# Audio-Beamformer_RaspberryPi_V1_0.net
KiCad netlist of a schematic drawn in Altium Designer
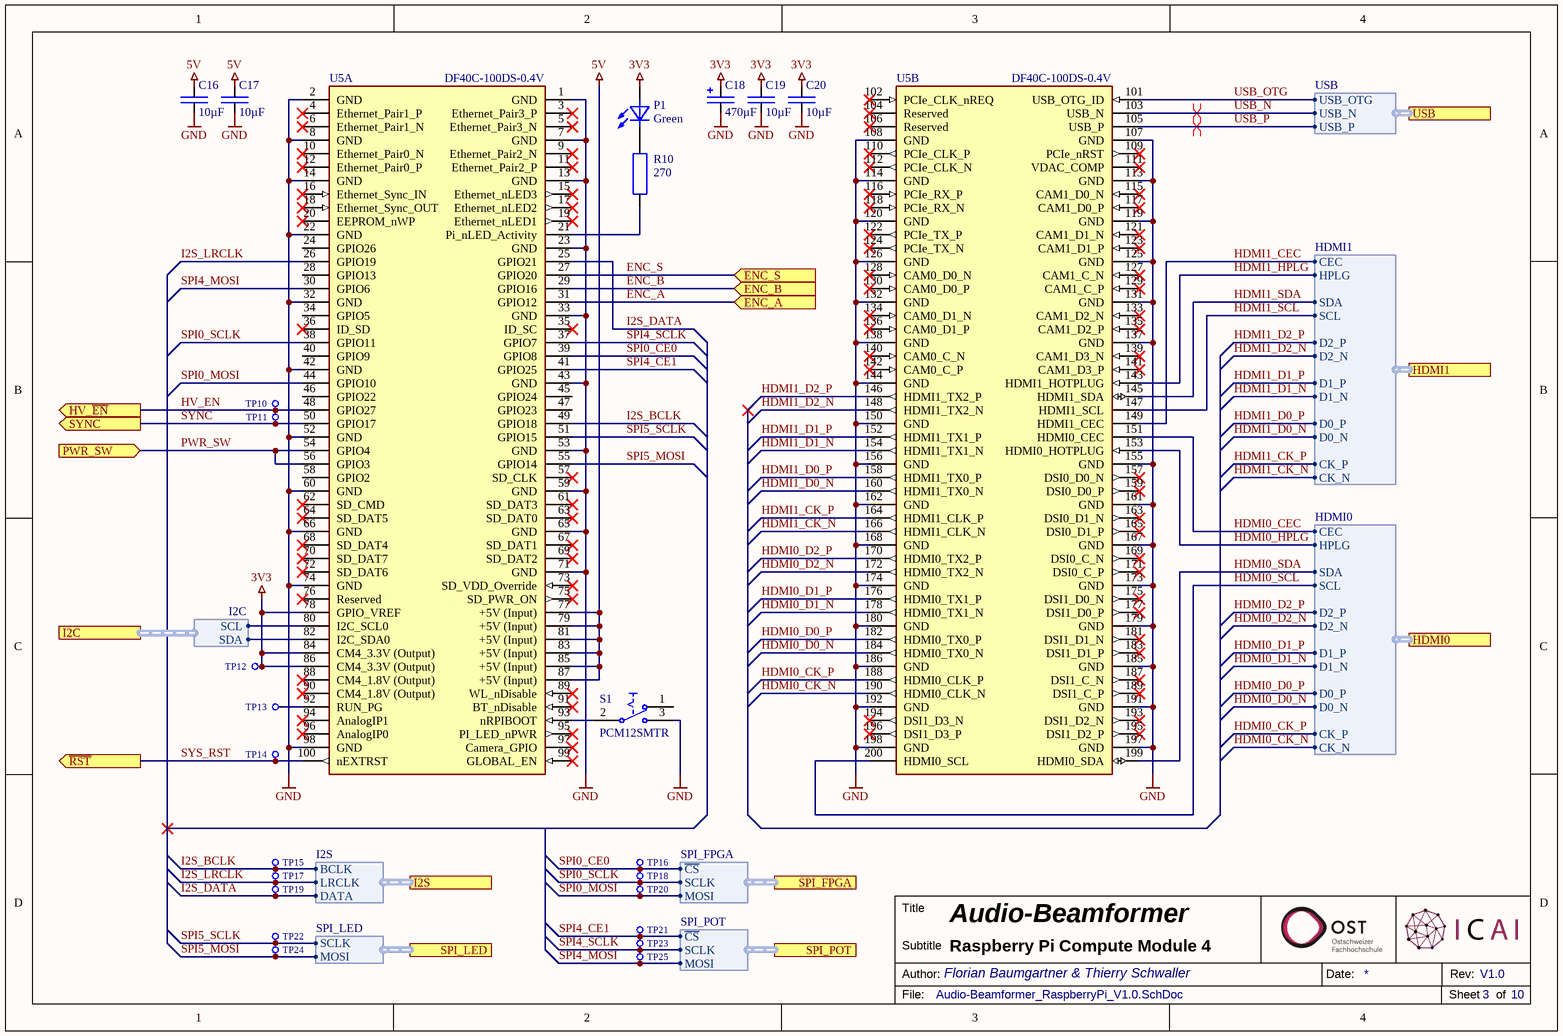
[diagram p0: Audio-Beamformer_RaspberryPi_V1.0.SchDoc]

(export (version "E")
  (design (tool "Eeschema 10.0.6"))
  (components
    (comp (ref "C16")
      (value "10µF")
      (footprint "SMD Keramikkondensator 1206")
      (description "CAP-MK")
      (libsource (lib "AudioAmp") (part "C-CAPACITOR"))
    )
    (comp (ref "C17")
      (value "10µF")
      (footprint "SMD Keramikkondensator 1206")
      (description "CAP-MK")
      (libsource (lib "AudioAmp") (part "C-CAPACITOR"))
    )
    (comp (ref "C18")
      (value "470µF")
      (footprint "SMD Elko 10.0x10.0")
      (description "CAP-Elko")
      (libsource (lib "TFS Integrated Library") (part "C-ELCAP"))
    )
    (comp (ref "C19")
      (value "10µF")
      (footprint "SMD Keramikkondensator 1206")
      (description "CAP-MK")
      (libsource (lib "AudioAmp") (part "C-CAPACITOR"))
    )
    (comp (ref "C20")
      (value "10µF")
      (footprint "SMD Keramikkondensator 1206")
      (description "CAP-MK")
      (libsource (lib "AudioAmp") (part "C-CAPACITOR"))
    )
    (comp (ref "P1")
      (value "Green")
      (footprint "SMD LED 0603")
      (description "General Purpose LED")
      (libsource (lib "Fleet-Monitor") (part "LED Green 0603"))
    )
    (comp (ref "R10")
      (value "270")
      (footprint "SMD Widerstand 0603")
      (description "SMD-Widerstand 1/4W")
      (libsource (lib "Backplane_1") (part "R-RESISTOR"))
    )
    (comp (ref "S1")
      (value "PCM12SMTR")
      (footprint "SMD Switch SPDT (PCM12SMTR)")
      (description "Miniature Slide Switch")
      (libsource (lib "Custom ST-Link") (part "S-PCM12SMTR"))
    )
    (comp (ref "TP10")
      (value "X-TP")
      (footprint "THT Testpunkt Ø1mm")
      (description "Testpunkt")
      (libsource (lib "Teensy-DevBoard") (part "X-TP"))
    )
    (comp (ref "TP11")
      (value "X-TP")
      (footprint "THT Testpunkt Ø1mm")
      (description "Testpunkt")
      (libsource (lib "Teensy-DevBoard") (part "X-TP"))
    )
    (comp (ref "TP12")
      (value "X-TP")
      (footprint "THT Testpunkt Ø1mm")
      (description "Testpunkt")
      (libsource (lib "Teensy-DevBoard") (part "X-TP"))
    )
    (comp (ref "TP13")
      (value "X-TP")
      (footprint "THT Testpunkt Ø1mm")
      (description "Testpunkt")
      (libsource (lib "Teensy-DevBoard") (part "X-TP"))
    )
    (comp (ref "TP14")
      (value "X-TP")
      (footprint "THT Testpunkt Ø1mm")
      (description "Testpunkt")
      (libsource (lib "Teensy-DevBoard") (part "X-TP"))
    )
    (comp (ref "TP15")
      (value "X-TP")
      (footprint "THT Testpunkt Ø1mm")
      (description "Testpunkt")
      (libsource (lib "Teensy-DevBoard") (part "X-TP"))
    )
    (comp (ref "TP16")
      (value "X-TP")
      (footprint "THT Testpunkt Ø1mm")
      (description "Testpunkt")
      (libsource (lib "Teensy-DevBoard") (part "X-TP"))
    )
    (comp (ref "TP17")
      (value "X-TP")
      (footprint "THT Testpunkt Ø1mm")
      (description "Testpunkt")
      (libsource (lib "Teensy-DevBoard") (part "X-TP"))
    )
    (comp (ref "TP18")
      (value "X-TP")
      (footprint "THT Testpunkt Ø1mm")
      (description "Testpunkt")
      (libsource (lib "Teensy-DevBoard") (part "X-TP"))
    )
    (comp (ref "TP19")
      (value "X-TP")
      (footprint "THT Testpunkt Ø1mm")
      (description "Testpunkt")
      (libsource (lib "Teensy-DevBoard") (part "X-TP"))
    )
    (comp (ref "TP20")
      (value "X-TP")
      (footprint "THT Testpunkt Ø1mm")
      (description "Testpunkt")
      (libsource (lib "Teensy-DevBoard") (part "X-TP"))
    )
    (comp (ref "TP21")
      (value "X-TP")
      (footprint "THT Testpunkt Ø1mm")
      (description "Testpunkt")
      (libsource (lib "Teensy-DevBoard") (part "X-TP"))
    )
    (comp (ref "TP22")
      (value "X-TP")
      (footprint "THT Testpunkt Ø1mm")
      (description "Testpunkt")
      (libsource (lib "Teensy-DevBoard") (part "X-TP"))
    )
    (comp (ref "TP23")
      (value "X-TP")
      (footprint "THT Testpunkt Ø1mm")
      (description "Testpunkt")
      (libsource (lib "Teensy-DevBoard") (part "X-TP"))
    )
    (comp (ref "TP24")
      (value "X-TP")
      (footprint "THT Testpunkt Ø1mm")
      (description "Testpunkt")
      (libsource (lib "Teensy-DevBoard") (part "X-TP"))
    )
    (comp (ref "TP25")
      (value "X-TP")
      (footprint "THT Testpunkt Ø1mm")
      (description "Testpunkt")
      (libsource (lib "Teensy-DevBoard") (part "X-TP"))
    )
    (comp (ref "U5")
      (value "DF40C-100DS-0.4V")
      (footprint "SMD CM4-F40C-100DS-0.4v_1.5mm")
      (description "Board-To-Board Connector")
      (libsource (lib "Audio-Beamformer") (part "U-CM4"))
    )
  )
  (nets
    (net (code "9") (name "/ENC_A") (class "Default")
      (node (ref "U5") (pin "31") (pinfunction "GPIO12_31") (pintype "passive"))
    )
    (net (code "10") (name "/ENC_B") (class "Default")
      (node (ref "U5") (pin "29") (pinfunction "GPIO16_29") (pintype "passive"))
    )
    (net (code "11") (name "/ENC_S") (class "Default")
      (node (ref "U5") (pin "27") (pinfunction "GPIO20_27") (pintype "passive"))
    )
    (net (code "12") (name "/HDMI0_CEC") (class "Default")
      (node (ref "U5") (pin "151") (pinfunction "HDMI0_CEC_151") (pintype "open_collector"))
    )
    (net (code "13") (name "/HDMI0_CK_N") (class "Default")
      (node (ref "U5") (pin "190") (pinfunction "HDMI0_CLK_N_190") (pintype "output"))
    )
    (net (code "14") (name "/HDMI0_CK_P") (class "Default")
      (node (ref "U5") (pin "188") (pinfunction "HDMI0_CLK_P_188") (pintype "output"))
    )
    (net (code "15") (name "/HDMI0_D0_N") (class "Default")
      (node (ref "U5") (pin "184") (pinfunction "HDMI0_TX0_N_184") (pintype "output"))
    )
    (net (code "16") (name "/HDMI0_D0_P") (class "Default")
      (node (ref "U5") (pin "182") (pinfunction "HDMI0_TX0_P_182") (pintype "output"))
    )
    (net (code "17") (name "/HDMI0_D1_N") (class "Default")
      (node (ref "U5") (pin "178") (pinfunction "HDMI0_TX1_N_178") (pintype "output"))
    )
    (net (code "18") (name "/HDMI0_D1_P") (class "Default")
      (node (ref "U5") (pin "176") (pinfunction "HDMI0_TX1_P_176") (pintype "output"))
    )
    (net (code "19") (name "/HDMI0_D2_N") (class "Default")
      (node (ref "U5") (pin "172") (pinfunction "HDMI0_TX2_N_172") (pintype "output"))
    )
    (net (code "20") (name "/HDMI0_D2_P") (class "Default")
      (node (ref "U5") (pin "170") (pinfunction "HDMI0_TX2_P_170") (pintype "output"))
    )
    (net (code "21") (name "/HDMI0_HPLG") (class "Default")
      (node (ref "U5") (pin "153") (pinfunction "HDMI0_HOTPLUG_153") (pintype "input"))
    )
    (net (code "22") (name "/HDMI0_SCL") (class "Default")
      (node (ref "U5") (pin "200") (pinfunction "HDMI0_SCL_200") (pintype "open_collector"))
    )
    (net (code "23") (name "/HDMI0_SDA") (class "Default")
      (node (ref "U5") (pin "199") (pinfunction "HDMI0_SDA_199") (pintype "bidirectional"))
    )
    (net (code "24") (name "/HDMI1_CEC") (class "Default")
      (node (ref "U5") (pin "149") (pinfunction "HDMI1_CEC_149") (pintype "open_collector"))
    )
    (net (code "25") (name "/HDMI1_CK_N") (class "Default")
      (node (ref "U5") (pin "166") (pinfunction "HDMI1_CLK_N_166") (pintype "output"))
    )
    (net (code "26") (name "/HDMI1_CK_P") (class "Default")
      (node (ref "U5") (pin "164") (pinfunction "HDMI1_CLK_P_164") (pintype "output"))
    )
    (net (code "27") (name "/HDMI1_D0_N") (class "Default")
      (node (ref "U5") (pin "160") (pinfunction "HDMI1_TX0_N_160") (pintype "output"))
    )
    (net (code "28") (name "/HDMI1_D0_P") (class "Default")
      (node (ref "U5") (pin "158") (pinfunction "HDMI1_TX0_P_158") (pintype "output"))
    )
    (net (code "29") (name "/HDMI1_D1_N") (class "Default")
      (node (ref "U5") (pin "154") (pinfunction "HDMI1_TX1_N_154") (pintype "output"))
    )
    (net (code "30") (name "/HDMI1_D1_P") (class "Default")
      (node (ref "U5") (pin "152") (pinfunction "HDMI1_TX1_P_152") (pintype "output"))
    )
    (net (code "31") (name "/HDMI1_D2_N") (class "Default")
      (node (ref "U5") (pin "148") (pinfunction "HDMI1_TX2_N_148") (pintype "output"))
    )
    (net (code "32") (name "/HDMI1_D2_P") (class "Default")
      (node (ref "U5") (pin "146") (pinfunction "HDMI1_TX2_P_146") (pintype "output"))
    )
    (net (code "33") (name "/HDMI1_HPLG") (class "Default")
      (node (ref "U5") (pin "143") (pinfunction "HDMI1_HOTPLUG_143") (pintype "input"))
    )
    (net (code "34") (name "/HDMI1_SCL") (class "Default")
      (node (ref "U5") (pin "147") (pinfunction "HDMI1_SCL_147") (pintype "open_collector"))
    )
    (net (code "35") (name "/HDMI1_SDA") (class "Default")
      (node (ref "U5") (pin "145") (pinfunction "HDMI1_SDA_145") (pintype "bidirectional"))
    )
    (net (code "36") (name "/HV_EN") (class "Default")
      (node (ref "TP10") (pin "1") (pinfunction "1_1") (pintype "passive"))
      (node (ref "U5") (pin "48") (pinfunction "GPIO27_48") (pintype "passive"))
    )
    (net (code "37") (name "/I2S_BCLK") (class "Default")
      (node (ref "TP15") (pin "1") (pinfunction "1_1") (pintype "passive"))
      (node (ref "U5") (pin "49") (pinfunction "GPIO18_49") (pintype "passive"))
    )
    (net (code "38") (name "/I2S_DATA") (class "Default")
      (node (ref "TP19") (pin "1") (pinfunction "1_1") (pintype "passive"))
      (node (ref "U5") (pin "25") (pinfunction "GPIO21_25") (pintype "passive"))
    )
    (net (code "39") (name "/I2S_LRCLK") (class "Default")
      (node (ref "TP17") (pin "1") (pinfunction "1_1") (pintype "passive"))
      (node (ref "U5") (pin "26") (pinfunction "GPIO19_26") (pintype "passive"))
    )
    (net (code "40") (name "/PWR_SW") (class "Default")
      (node (ref "U5") (pin "54") (pinfunction "GPIO4_54") (pintype "passive"))
      (node (ref "U5") (pin "56") (pinfunction "GPIO3_56") (pintype "passive"))
    )
    (net (code "41") (name "/SPI0_CE0") (class "Default")
      (node (ref "TP16") (pin "1") (pinfunction "1_1") (pintype "passive"))
      (node (ref "U5") (pin "39") (pinfunction "GPIO8_39") (pintype "passive"))
    )
    (net (code "42") (name "/SPI0_MOSI") (class "Default")
      (node (ref "TP20") (pin "1") (pinfunction "1_1") (pintype "passive"))
      (node (ref "U5") (pin "44") (pinfunction "GPIO10_44") (pintype "passive"))
    )
    (net (code "43") (name "/SPI0_SCLK") (class "Default")
      (node (ref "TP18") (pin "1") (pinfunction "1_1") (pintype "passive"))
      (node (ref "U5") (pin "38") (pinfunction "GPIO11_38") (pintype "passive"))
    )
    (net (code "44") (name "/SPI4_CE1") (class "Default")
      (node (ref "TP21") (pin "1") (pinfunction "1_1") (pintype "passive"))
      (node (ref "U5") (pin "41") (pinfunction "GPIO25_41") (pintype "passive"))
    )
    (net (code "45") (name "/SPI4_MOSI") (class "Default")
      (node (ref "TP25") (pin "1") (pinfunction "1_1") (pintype "passive"))
      (node (ref "U5") (pin "30") (pinfunction "GPIO6_30") (pintype "passive"))
    )
    (net (code "46") (name "/SPI4_SCLK") (class "Default")
      (node (ref "TP23") (pin "1") (pinfunction "1_1") (pintype "passive"))
      (node (ref "U5") (pin "37") (pinfunction "GPIO7_37") (pintype "passive"))
    )
    (net (code "47") (name "/SPI5_MOSI") (class "Default")
      (node (ref "TP24") (pin "1") (pinfunction "1_1") (pintype "passive"))
      (node (ref "U5") (pin "55") (pinfunction "GPIO14_55") (pintype "passive"))
    )
    (net (code "48") (name "/SPI5_SCLK") (class "Default")
      (node (ref "TP22") (pin "1") (pinfunction "1_1") (pintype "passive"))
      (node (ref "U5") (pin "51") (pinfunction "GPIO15_51") (pintype "passive"))
    )
    (net (code "49") (name "/SYNC") (class "Default")
      (node (ref "TP11") (pin "1") (pinfunction "1_1") (pintype "passive"))
      (node (ref "U5") (pin "50") (pinfunction "GPIO17_50") (pintype "passive"))
    )
    (net (code "50") (name "/SYS_RST") (class "Default")
      (node (ref "TP14") (pin "1") (pinfunction "1_1") (pintype "passive"))
      (node (ref "U5") (pin "100") (pinfunction "nEXTRST_100") (pintype "output"))
    )
    (net (code "51") (name "/USB_N") (class "Default")
      (node (ref "U5") (pin "103") (pinfunction "USB_N_103") (pintype "passive"))
    )
    (net (code "52") (name "/USB_OTG") (class "Default")
      (node (ref "U5") (pin "101") (pinfunction "USB_OTG_ID_101") (pintype "input"))
    )
    (net (code "53") (name "/USB_P") (class "Default")
      (node (ref "U5") (pin "105") (pinfunction "USB_P_105") (pintype "passive"))
    )
    (net (code "62") (name "3V3") (class "Default")
      (node (ref "C18") (pin "P") (pinfunction "+_P") (pintype "passive"))
      (node (ref "C19") (pin "2") (pinfunction "2_2") (pintype "passive"))
      (node (ref "C20") (pin "2") (pinfunction "2_2") (pintype "passive"))
      (node (ref "P1") (pin "A") (pinfunction "A_A") (pintype "passive"))
      (node (ref "TP12") (pin "1") (pinfunction "1_1") (pintype "passive"))
      (node (ref "U5") (pin "78") (pinfunction "GPIO_VREF_78") (pintype "power_in"))
      (node (ref "U5") (pin "84") (pinfunction "CM4_3.3V_(Output)_84") (pintype "power_in"))
      (node (ref "U5") (pin "86") (pinfunction "CM4_3.3V_(Output)_86") (pintype "power_in"))
    )
    (net (code "63") (name "5V") (class "Default")
      (node (ref "C16") (pin "2") (pinfunction "2_2") (pintype "passive"))
      (node (ref "C17") (pin "2") (pinfunction "2_2") (pintype "passive"))
      (node (ref "U5") (pin "77") (pinfunction "+5V_(Input)_77") (pintype "power_in"))
      (node (ref "U5") (pin "79") (pinfunction "+5V_(Input)_79") (pintype "power_in"))
      (node (ref "U5") (pin "81") (pinfunction "+5V_(Input)_81") (pintype "power_in"))
      (node (ref "U5") (pin "83") (pinfunction "+5V_(Input)_83") (pintype "power_in"))
      (node (ref "U5") (pin "85") (pinfunction "+5V_(Input)_85") (pintype "power_in"))
      (node (ref "U5") (pin "87") (pinfunction "+5V_(Input)_87") (pintype "power_in"))
    )
    (net (code "64") (name "GND") (class "Default")
      (node (ref "C16") (pin "1") (pinfunction "1_1") (pintype "passive"))
      (node (ref "C17") (pin "1") (pinfunction "1_1") (pintype "passive"))
      (node (ref "C18") (pin "M") (pinfunction "-_M") (pintype "passive"))
      (node (ref "C19") (pin "1") (pinfunction "1_1") (pintype "passive"))
      (node (ref "C20") (pin "1") (pinfunction "1_1") (pintype "passive"))
      (node (ref "S1") (pin "3") (pinfunction "NO1_3") (pintype "passive"))
      (node (ref "U5") (pin "1") (pinfunction "GND_1") (pintype "power_in"))
      (node (ref "U5") (pin "107") (pinfunction "GND_107") (pintype "power_in"))
      (node (ref "U5") (pin "108") (pinfunction "GND_108") (pintype "power_in"))
      (node (ref "U5") (pin "113") (pinfunction "GND_113") (pintype "power_in"))
      (node (ref "U5") (pin "114") (pinfunction "GND_114") (pintype "power_in"))
      (node (ref "U5") (pin "119") (pinfunction "GND_119") (pintype "power_in"))
      (node (ref "U5") (pin "120") (pinfunction "GND_120") (pintype "power_in"))
      (node (ref "U5") (pin "125") (pinfunction "GND_125") (pintype "power_in"))
      (node (ref "U5") (pin "126") (pinfunction "GND_126") (pintype "power_in"))
      (node (ref "U5") (pin "13") (pinfunction "GND_13") (pintype "power_in"))
      (node (ref "U5") (pin "131") (pinfunction "GND_131") (pintype "power_in"))
      (node (ref "U5") (pin "132") (pinfunction "GND_132") (pintype "power_in"))
      (node (ref "U5") (pin "137") (pinfunction "GND_137") (pintype "power_in"))
      (node (ref "U5") (pin "138") (pinfunction "GND_138") (pintype "power_in"))
      (node (ref "U5") (pin "14") (pinfunction "GND_14") (pintype "power_in"))
      (node (ref "U5") (pin "144") (pinfunction "GND_144") (pintype "power_in"))
      (node (ref "U5") (pin "150") (pinfunction "GND_150") (pintype "power_in"))
      (node (ref "U5") (pin "155") (pinfunction "GND_155") (pintype "power_in"))
      (node (ref "U5") (pin "156") (pinfunction "GND_156") (pintype "power_in"))
      (node (ref "U5") (pin "161") (pinfunction "GND_161") (pintype "power_in"))
      (node (ref "U5") (pin "162") (pinfunction "GND_162") (pintype "power_in"))
      (node (ref "U5") (pin "167") (pinfunction "GND_167") (pintype "power_in"))
      (node (ref "U5") (pin "168") (pinfunction "GND_168") (pintype "power_in"))
      (node (ref "U5") (pin "173") (pinfunction "GND_173") (pintype "power_in"))
      (node (ref "U5") (pin "174") (pinfunction "GND_174") (pintype "power_in"))
      (node (ref "U5") (pin "179") (pinfunction "GND_179") (pintype "power_in"))
      (node (ref "U5") (pin "180") (pinfunction "GND_180") (pintype "power_in"))
      (node (ref "U5") (pin "185") (pinfunction "GND_185") (pintype "power_in"))
      (node (ref "U5") (pin "186") (pinfunction "GND_186") (pintype "power_in"))
      (node (ref "U5") (pin "191") (pinfunction "GND_191") (pintype "power_in"))
      (node (ref "U5") (pin "192") (pinfunction "GND_192") (pintype "power_in"))
      (node (ref "U5") (pin "197") (pinfunction "GND_197") (pintype "power_in"))
      (node (ref "U5") (pin "198") (pinfunction "GND_198") (pintype "power_in"))
      (node (ref "U5") (pin "2") (pinfunction "GND_2") (pintype "power_in"))
      (node (ref "U5") (pin "22") (pinfunction "GND_22") (pintype "power_in"))
      (node (ref "U5") (pin "23") (pinfunction "GND_23") (pintype "power_in"))
      (node (ref "U5") (pin "32") (pinfunction "GND_32") (pintype "power_in"))
      (node (ref "U5") (pin "33") (pinfunction "GND_33") (pintype "power_in"))
      (node (ref "U5") (pin "42") (pinfunction "GND_42") (pintype "power_in"))
      (node (ref "U5") (pin "43") (pinfunction "GND_43") (pintype "power_in"))
      (node (ref "U5") (pin "52") (pinfunction "GND_52") (pintype "power_in"))
      (node (ref "U5") (pin "53") (pinfunction "GND_53") (pintype "power_in"))
      (node (ref "U5") (pin "59") (pinfunction "GND_59") (pintype "power_in"))
      (node (ref "U5") (pin "60") (pinfunction "GND_60") (pintype "power_in"))
      (node (ref "U5") (pin "65") (pinfunction "GND_65") (pintype "power_in"))
      (node (ref "U5") (pin "66") (pinfunction "GND_66") (pintype "power_in"))
      (node (ref "U5") (pin "7") (pinfunction "GND_7") (pintype "power_in"))
      (node (ref "U5") (pin "71") (pinfunction "GND_71") (pintype "power_in"))
      (node (ref "U5") (pin "74") (pinfunction "GND_74") (pintype "power_in"))
      (node (ref "U5") (pin "8") (pinfunction "GND_8") (pintype "power_in"))
      (node (ref "U5") (pin "98") (pinfunction "GND_98") (pintype "power_in"))
    )
    (net (code "65") (name "Net-(P1-PadK)") (class "Default")
      (node (ref "P1") (pin "K") (pinfunction "K_K") (pintype "passive"))
      (node (ref "R10") (pin "1") (pinfunction "1_1") (pintype "passive"))
    )
    (net (code "66") (name "Net-(S1-COMMON1)") (class "Default")
      (node (ref "S1") (pin "2") (pinfunction "COMMON1_2") (pintype "passive"))
      (node (ref "U5") (pin "93") (pinfunction "nRPIBOOT_93") (pintype "input"))
    )
    (net (code "67") (name "Net-(U5A-Pi_nLED_Activity)") (class "Default")
      (node (ref "R10") (pin "2") (pinfunction "2_2") (pintype "passive"))
      (node (ref "U5") (pin "21") (pinfunction "Pi_nLED_Activity_21") (pintype "open_collector"))
    )
    (net (code "68") (name "Net-(U5A-RUN_PG)") (class "Default")
      (node (ref "TP13") (pin "1") (pinfunction "1_1") (pintype "passive"))
      (node (ref "U5") (pin "92") (pinfunction "RUN_PG_92") (pintype "passive"))
    )
    (net (code "69") (name "unconnected-(S1-NC1-Pad1)") (class "Default")
      (node (ref "S1") (pin "1") (pinfunction "NC1_1") (pintype "passive"))
    )
    (net (code "70") (name "unconnected-(U5A-AnalogIP0-Pad96)") (class "Default")
      (node (ref "U5") (pin "96") (pinfunction "AnalogIP0_96") (pintype "passive+no_connect"))
    )
    (net (code "71") (name "unconnected-(U5A-AnalogIP1-Pad94)") (class "Default")
      (node (ref "U5") (pin "94") (pinfunction "AnalogIP1_94") (pintype "passive+no_connect"))
    )
    (net (code "72") (name "unconnected-(U5A-BT_nDisable-Pad91)") (class "Default")
      (node (ref "U5") (pin "91") (pinfunction "BT_nDisable_91") (pintype "input+no_connect"))
    )
    (net (code "73") (name "unconnected-(U5A-CM4_1.8V_(Output)-Pad88)") (class "Default")
      (node (ref "U5") (pin "88") (pinfunction "CM4_1.8V_(Output)_88") (pintype "power_in+no_connect"))
    )
    (net (code "74") (name "unconnected-(U5A-CM4_1.8V_(Output)-Pad90)") (class "Default")
      (node (ref "U5") (pin "90") (pinfunction "CM4_1.8V_(Output)_90") (pintype "power_in+no_connect"))
    )
    (net (code "75") (name "unconnected-(U5A-Camera_GPIO-Pad97)") (class "Default")
      (node (ref "U5") (pin "97") (pinfunction "Camera_GPIO_97") (pintype "passive+no_connect"))
    )
    (net (code "76") (name "unconnected-(U5A-EEPROM_nWP-Pad20)") (class "Default")
      (node (ref "U5") (pin "20") (pinfunction "EEPROM_nWP_20") (pintype "passive+no_connect"))
    )
    (net (code "77") (name "unconnected-(U5A-Ethernet_Pair0_N-Pad10)") (class "Default")
      (node (ref "U5") (pin "10") (pinfunction "Ethernet_Pair0_N_10") (pintype "passive+no_connect"))
    )
    (net (code "78") (name "unconnected-(U5A-Ethernet_Pair0_P-Pad12)") (class "Default")
      (node (ref "U5") (pin "12") (pinfunction "Ethernet_Pair0_P_12") (pintype "passive+no_connect"))
    )
    (net (code "79") (name "unconnected-(U5A-Ethernet_Pair1_N-Pad6)") (class "Default")
      (node (ref "U5") (pin "6") (pinfunction "Ethernet_Pair1_N_6") (pintype "passive+no_connect"))
    )
    (net (code "80") (name "unconnected-(U5A-Ethernet_Pair1_P-Pad4)") (class "Default")
      (node (ref "U5") (pin "4") (pinfunction "Ethernet_Pair1_P_4") (pintype "passive+no_connect"))
    )
    (net (code "81") (name "unconnected-(U5A-Ethernet_Pair2_N-Pad9)") (class "Default")
      (node (ref "U5") (pin "9") (pinfunction "Ethernet_Pair2_N_9") (pintype "passive+no_connect"))
    )
    (net (code "82") (name "unconnected-(U5A-Ethernet_Pair2_P-Pad11)") (class "Default")
      (node (ref "U5") (pin "11") (pinfunction "Ethernet_Pair2_P_11") (pintype "passive+no_connect"))
    )
    (net (code "83") (name "unconnected-(U5A-Ethernet_Pair3_N-Pad5)") (class "Default")
      (node (ref "U5") (pin "5") (pinfunction "Ethernet_Pair3_N_5") (pintype "passive+no_connect"))
    )
    (net (code "84") (name "unconnected-(U5A-Ethernet_Pair3_P-Pad3)") (class "Default")
      (node (ref "U5") (pin "3") (pinfunction "Ethernet_Pair3_P_3") (pintype "passive+no_connect"))
    )
    (net (code "85") (name "unconnected-(U5A-Ethernet_Sync_IN-Pad16)") (class "Default")
      (node (ref "U5") (pin "16") (pinfunction "Ethernet_Sync_IN_16") (pintype "input+no_connect"))
    )
    (net (code "86") (name "unconnected-(U5A-Ethernet_Sync_OUT-Pad18)") (class "Default")
      (node (ref "U5") (pin "18") (pinfunction "Ethernet_Sync_OUT_18") (pintype "input+no_connect"))
    )
    (net (code "87") (name "unconnected-(U5A-Ethernet_nLED1-Pad19)") (class "Default")
      (node (ref "U5") (pin "19") (pinfunction "Ethernet_nLED1_19") (pintype "output+no_connect"))
    )
    (net (code "88") (name "unconnected-(U5A-Ethernet_nLED2-Pad17)") (class "Default")
      (node (ref "U5") (pin "17") (pinfunction "Ethernet_nLED2_17") (pintype "output+no_connect"))
    )
    (net (code "89") (name "unconnected-(U5A-Ethernet_nLED3-Pad15)") (class "Default")
      (node (ref "U5") (pin "15") (pinfunction "Ethernet_nLED3_15") (pintype "output+no_connect"))
    )
    (net (code "90") (name "unconnected-(U5A-GLOBAL_EN-Pad99)") (class "Default")
      (node (ref "U5") (pin "99") (pinfunction "GLOBAL_EN_99") (pintype "input+no_connect"))
    )
    (net (code "91") (name "unconnected-(U5A-GPIO2-Pad58)") (class "Default")
      (node (ref "U5") (pin "58") (pinfunction "GPIO2_58") (pintype "passive"))
    )
    (net (code "92") (name "unconnected-(U5A-GPIO5-Pad34)") (class "Default")
      (node (ref "U5") (pin "34") (pinfunction "GPIO5_34") (pintype "passive"))
    )
    (net (code "93") (name "unconnected-(U5A-GPIO9-Pad40)") (class "Default")
      (node (ref "U5") (pin "40") (pinfunction "GPIO9_40") (pintype "passive"))
    )
    (net (code "94") (name "unconnected-(U5A-GPIO13-Pad28)") (class "Default")
      (node (ref "U5") (pin "28") (pinfunction "GPIO13_28") (pintype "passive"))
    )
    (net (code "95") (name "unconnected-(U5A-GPIO22-Pad46)") (class "Default")
      (node (ref "U5") (pin "46") (pinfunction "GPIO22_46") (pintype "passive"))
    )
    (net (code "96") (name "unconnected-(U5A-GPIO23-Pad47)") (class "Default")
      (node (ref "U5") (pin "47") (pinfunction "GPIO23_47") (pintype "passive"))
    )
    (net (code "97") (name "unconnected-(U5A-GPIO24-Pad45)") (class "Default")
      (node (ref "U5") (pin "45") (pinfunction "GPIO24_45") (pintype "passive"))
    )
    (net (code "98") (name "unconnected-(U5A-GPIO26-Pad24)") (class "Default")
      (node (ref "U5") (pin "24") (pinfunction "GPIO26_24") (pintype "passive"))
    )
    (net (code "99") (name "unconnected-(U5A-I2C_SCL0-Pad80)") (class "Default")
      (node (ref "U5") (pin "80") (pinfunction "I2C_SCL0_80") (pintype "passive"))
    )
    (net (code "100") (name "unconnected-(U5A-I2C_SDA0-Pad82)") (class "Default")
      (node (ref "U5") (pin "82") (pinfunction "I2C_SDA0_82") (pintype "passive"))
    )
    (net (code "101") (name "unconnected-(U5A-ID_SC-Pad35)") (class "Default")
      (node (ref "U5") (pin "35") (pinfunction "ID_SC_35") (pintype "passive+no_connect"))
    )
    (net (code "102") (name "unconnected-(U5A-ID_SD-Pad36)") (class "Default")
      (node (ref "U5") (pin "36") (pinfunction "ID_SD_36") (pintype "passive+no_connect"))
    )
    (net (code "103") (name "unconnected-(U5A-PI_LED_nPWR-Pad95)") (class "Default")
      (node (ref "U5") (pin "95") (pinfunction "PI_LED_nPWR_95") (pintype "output+no_connect"))
    )
    (net (code "104") (name "unconnected-(U5A-Reserved-Pad76)") (class "Default")
      (node (ref "U5") (pin "76") (pinfunction "Reserved_76") (pintype "passive+no_connect"))
    )
    (net (code "105") (name "unconnected-(U5A-SD_CLK-Pad57)") (class "Default")
      (node (ref "U5") (pin "57") (pinfunction "SD_CLK_57") (pintype "passive+no_connect"))
    )
    (net (code "106") (name "unconnected-(U5A-SD_CMD-Pad62)") (class "Default")
      (node (ref "U5") (pin "62") (pinfunction "SD_CMD_62") (pintype "passive+no_connect"))
    )
    (net (code "107") (name "unconnected-(U5A-SD_DAT0-Pad63)") (class "Default")
      (node (ref "U5") (pin "63") (pinfunction "SD_DAT0_63") (pintype "passive+no_connect"))
    )
    (net (code "108") (name "unconnected-(U5A-SD_DAT1-Pad67)") (class "Default")
      (node (ref "U5") (pin "67") (pinfunction "SD_DAT1_67") (pintype "passive+no_connect"))
    )
    (net (code "109") (name "unconnected-(U5A-SD_DAT2-Pad69)") (class "Default")
      (node (ref "U5") (pin "69") (pinfunction "SD_DAT2_69") (pintype "passive+no_connect"))
    )
    (net (code "110") (name "unconnected-(U5A-SD_DAT3-Pad61)") (class "Default")
      (node (ref "U5") (pin "61") (pinfunction "SD_DAT3_61") (pintype "passive+no_connect"))
    )
    (net (code "111") (name "unconnected-(U5A-SD_DAT4-Pad68)") (class "Default")
      (node (ref "U5") (pin "68") (pinfunction "SD_DAT4_68") (pintype "passive+no_connect"))
    )
    (net (code "112") (name "unconnected-(U5A-SD_DAT5-Pad64)") (class "Default")
      (node (ref "U5") (pin "64") (pinfunction "SD_DAT5_64") (pintype "passive+no_connect"))
    )
    (net (code "113") (name "unconnected-(U5A-SD_DAT6-Pad72)") (class "Default")
      (node (ref "U5") (pin "72") (pinfunction "SD_DAT6_72") (pintype "passive+no_connect"))
    )
    (net (code "114") (name "unconnected-(U5A-SD_DAT7-Pad70)") (class "Default")
      (node (ref "U5") (pin "70") (pinfunction "SD_DAT7_70") (pintype "passive+no_connect"))
    )
    (net (code "115") (name "unconnected-(U5A-SD_PWR_ON-Pad75)") (class "Default")
      (node (ref "U5") (pin "75") (pinfunction "SD_PWR_ON_75") (pintype "output+no_connect"))
    )
    (net (code "116") (name "unconnected-(U5A-SD_VDD_Override-Pad73)") (class "Default")
      (node (ref "U5") (pin "73") (pinfunction "SD_VDD_Override_73") (pintype "input+no_connect"))
    )
    (net (code "117") (name "unconnected-(U5A-WL_nDisable-Pad89)") (class "Default")
      (node (ref "U5") (pin "89") (pinfunction "WL_nDisable_89") (pintype "input+no_connect"))
    )
    (net (code "118") (name "unconnected-(U5B-CAM0_C_N-Pad140)") (class "Default")
      (node (ref "U5") (pin "140") (pinfunction "CAM0_C_N_140") (pintype "input+no_connect"))
    )
    (net (code "119") (name "unconnected-(U5B-CAM0_C_P-Pad142)") (class "Default")
      (node (ref "U5") (pin "142") (pinfunction "CAM0_C_P_142") (pintype "input+no_connect"))
    )
    (net (code "120") (name "unconnected-(U5B-CAM0_D0_N-Pad128)") (class "Default")
      (node (ref "U5") (pin "128") (pinfunction "CAM0_D0_N_128") (pintype "input+no_connect"))
    )
    (net (code "121") (name "unconnected-(U5B-CAM0_D0_P-Pad130)") (class "Default")
      (node (ref "U5") (pin "130") (pinfunction "CAM0_D0_P_130") (pintype "input+no_connect"))
    )
    (net (code "122") (name "unconnected-(U5B-CAM0_D1_N-Pad134)") (class "Default")
      (node (ref "U5") (pin "134") (pinfunction "CAM0_D1_N_134") (pintype "input+no_connect"))
    )
    (net (code "123") (name "unconnected-(U5B-CAM0_D1_P-Pad136)") (class "Default")
      (node (ref "U5") (pin "136") (pinfunction "CAM0_D1_P_136") (pintype "input+no_connect"))
    )
    (net (code "124") (name "unconnected-(U5B-CAM1_C_N-Pad127)") (class "Default")
      (node (ref "U5") (pin "127") (pinfunction "CAM1_C_N_127") (pintype "input+no_connect"))
    )
    (net (code "125") (name "unconnected-(U5B-CAM1_C_P-Pad129)") (class "Default")
      (node (ref "U5") (pin "129") (pinfunction "CAM1_C_P_129") (pintype "input+no_connect"))
    )
    (net (code "126") (name "unconnected-(U5B-CAM1_D0_N-Pad115)") (class "Default")
      (node (ref "U5") (pin "115") (pinfunction "CAM1_D0_N_115") (pintype "input+no_connect"))
    )
    (net (code "127") (name "unconnected-(U5B-CAM1_D0_P-Pad117)") (class "Default")
      (node (ref "U5") (pin "117") (pinfunction "CAM1_D0_P_117") (pintype "input+no_connect"))
    )
    (net (code "128") (name "unconnected-(U5B-CAM1_D1_N-Pad121)") (class "Default")
      (node (ref "U5") (pin "121") (pinfunction "CAM1_D1_N_121") (pintype "input+no_connect"))
    )
    (net (code "129") (name "unconnected-(U5B-CAM1_D1_P-Pad123)") (class "Default")
      (node (ref "U5") (pin "123") (pinfunction "CAM1_D1_P_123") (pintype "input+no_connect"))
    )
    (net (code "130") (name "unconnected-(U5B-CAM1_D2_N-Pad133)") (class "Default")
      (node (ref "U5") (pin "133") (pinfunction "CAM1_D2_N_133") (pintype "input+no_connect"))
    )
    (net (code "131") (name "unconnected-(U5B-CAM1_D2_P-Pad135)") (class "Default")
      (node (ref "U5") (pin "135") (pinfunction "CAM1_D2_P_135") (pintype "input+no_connect"))
    )
    (net (code "132") (name "unconnected-(U5B-CAM1_D3_N-Pad139)") (class "Default")
      (node (ref "U5") (pin "139") (pinfunction "CAM1_D3_N_139") (pintype "input+no_connect"))
    )
    (net (code "133") (name "unconnected-(U5B-CAM1_D3_P-Pad141)") (class "Default")
      (node (ref "U5") (pin "141") (pinfunction "CAM1_D3_P_141") (pintype "input+no_connect"))
    )
    (net (code "134") (name "unconnected-(U5B-DSI0_C_N-Pad169)") (class "Default")
      (node (ref "U5") (pin "169") (pinfunction "DSI0_C_N_169") (pintype "output+no_connect"))
    )
    (net (code "135") (name "unconnected-(U5B-DSI0_C_P-Pad171)") (class "Default")
      (node (ref "U5") (pin "171") (pinfunction "DSI0_C_P_171") (pintype "output+no_connect"))
    )
    (net (code "136") (name "unconnected-(U5B-DSI0_D0_N-Pad157)") (class "Default")
      (node (ref "U5") (pin "157") (pinfunction "DSI0_D0_N_157") (pintype "output+no_connect"))
    )
    (net (code "137") (name "unconnected-(U5B-DSI0_D0_P-Pad159)") (class "Default")
      (node (ref "U5") (pin "159") (pinfunction "DSI0_D0_P_159") (pintype "output+no_connect"))
    )
    (net (code "138") (name "unconnected-(U5B-DSI0_D1_N-Pad163)") (class "Default")
      (node (ref "U5") (pin "163") (pinfunction "DSI0_D1_N_163") (pintype "output+no_connect"))
    )
    (net (code "139") (name "unconnected-(U5B-DSI0_D1_P-Pad165)") (class "Default")
      (node (ref "U5") (pin "165") (pinfunction "DSI0_D1_P_165") (pintype "output+no_connect"))
    )
    (net (code "140") (name "unconnected-(U5B-DSI1_C_N-Pad187)") (class "Default")
      (node (ref "U5") (pin "187") (pinfunction "DSI1_C_N_187") (pintype "output+no_connect"))
    )
    (net (code "141") (name "unconnected-(U5B-DSI1_C_P-Pad189)") (class "Default")
      (node (ref "U5") (pin "189") (pinfunction "DSI1_C_P_189") (pintype "output+no_connect"))
    )
    (net (code "142") (name "unconnected-(U5B-DSI1_D0_N-Pad175)") (class "Default")
      (node (ref "U5") (pin "175") (pinfunction "DSI1_D0_N_175") (pintype "output+no_connect"))
    )
    (net (code "143") (name "unconnected-(U5B-DSI1_D0_P-Pad177)") (class "Default")
      (node (ref "U5") (pin "177") (pinfunction "DSI1_D0_P_177") (pintype "output+no_connect"))
    )
    (net (code "144") (name "unconnected-(U5B-DSI1_D1_N-Pad181)") (class "Default")
      (node (ref "U5") (pin "181") (pinfunction "DSI1_D1_N_181") (pintype "output+no_connect"))
    )
    (net (code "145") (name "unconnected-(U5B-DSI1_D1_P-Pad183)") (class "Default")
      (node (ref "U5") (pin "183") (pinfunction "DSI1_D1_P_183") (pintype "output+no_connect"))
    )
    (net (code "146") (name "unconnected-(U5B-DSI1_D2_N-Pad193)") (class "Default")
      (node (ref "U5") (pin "193") (pinfunction "DSI1_D2_N_193") (pintype "output+no_connect"))
    )
    (net (code "147") (name "unconnected-(U5B-DSI1_D2_P-Pad195)") (class "Default")
      (node (ref "U5") (pin "195") (pinfunction "DSI1_D2_P_195") (pintype "output+no_connect"))
    )
    (net (code "148") (name "unconnected-(U5B-DSI1_D3_N-Pad194)") (class "Default")
      (node (ref "U5") (pin "194") (pinfunction "DSI1_D3_N_194") (pintype "output+no_connect"))
    )
    (net (code "149") (name "unconnected-(U5B-DSI1_D3_P-Pad196)") (class "Default")
      (node (ref "U5") (pin "196") (pinfunction "DSI1_D3_P_196") (pintype "output+no_connect"))
    )
    (net (code "150") (name "unconnected-(U5B-PCIe_CLK_N-Pad112)") (class "Default")
      (node (ref "U5") (pin "112") (pinfunction "PCIe_CLK_N_112") (pintype "output+no_connect"))
    )
    (net (code "151") (name "unconnected-(U5B-PCIe_CLK_P-Pad110)") (class "Default")
      (node (ref "U5") (pin "110") (pinfunction "PCIe_CLK_P_110") (pintype "output+no_connect"))
    )
    (net (code "152") (name "unconnected-(U5B-PCIe_CLK_nREQ-Pad102)") (class "Default")
      (node (ref "U5") (pin "102") (pinfunction "PCIe_CLK_nREQ_102") (pintype "input+no_connect"))
    )
    (net (code "153") (name "unconnected-(U5B-PCIe_RX_N-Pad118)") (class "Default")
      (node (ref "U5") (pin "118") (pinfunction "PCIe_RX_N_118") (pintype "input+no_connect"))
    )
    (net (code "154") (name "unconnected-(U5B-PCIe_RX_P-Pad116)") (class "Default")
      (node (ref "U5") (pin "116") (pinfunction "PCIe_RX_P_116") (pintype "input+no_connect"))
    )
    (net (code "155") (name "unconnected-(U5B-PCIe_TX_N-Pad124)") (class "Default")
      (node (ref "U5") (pin "124") (pinfunction "PCIe_TX_N_124") (pintype "output+no_connect"))
    )
    (net (code "156") (name "unconnected-(U5B-PCIe_TX_P-Pad122)") (class "Default")
      (node (ref "U5") (pin "122") (pinfunction "PCIe_TX_P_122") (pintype "output+no_connect"))
    )
    (net (code "157") (name "unconnected-(U5B-PCIe_nRST-Pad109)") (class "Default")
      (node (ref "U5") (pin "109") (pinfunction "PCIe_nRST_109") (pintype "output+no_connect"))
    )
    (net (code "158") (name "unconnected-(U5B-Reserved-Pad104)") (class "Default")
      (node (ref "U5") (pin "104") (pinfunction "Reserved_104") (pintype "passive+no_connect"))
    )
    (net (code "159") (name "unconnected-(U5B-Reserved-Pad106)") (class "Default")
      (node (ref "U5") (pin "106") (pinfunction "Reserved_106") (pintype "passive+no_connect"))
    )
    (net (code "160") (name "unconnected-(U5B-VDAC_COMP-Pad111)") (class "Default")
      (node (ref "U5") (pin "111") (pinfunction "VDAC_COMP_111") (pintype "passive+no_connect"))
    )
  )
)
